# Newtech_Music_Board.net
KiCad netlist of a schematic drawn in EAGLE
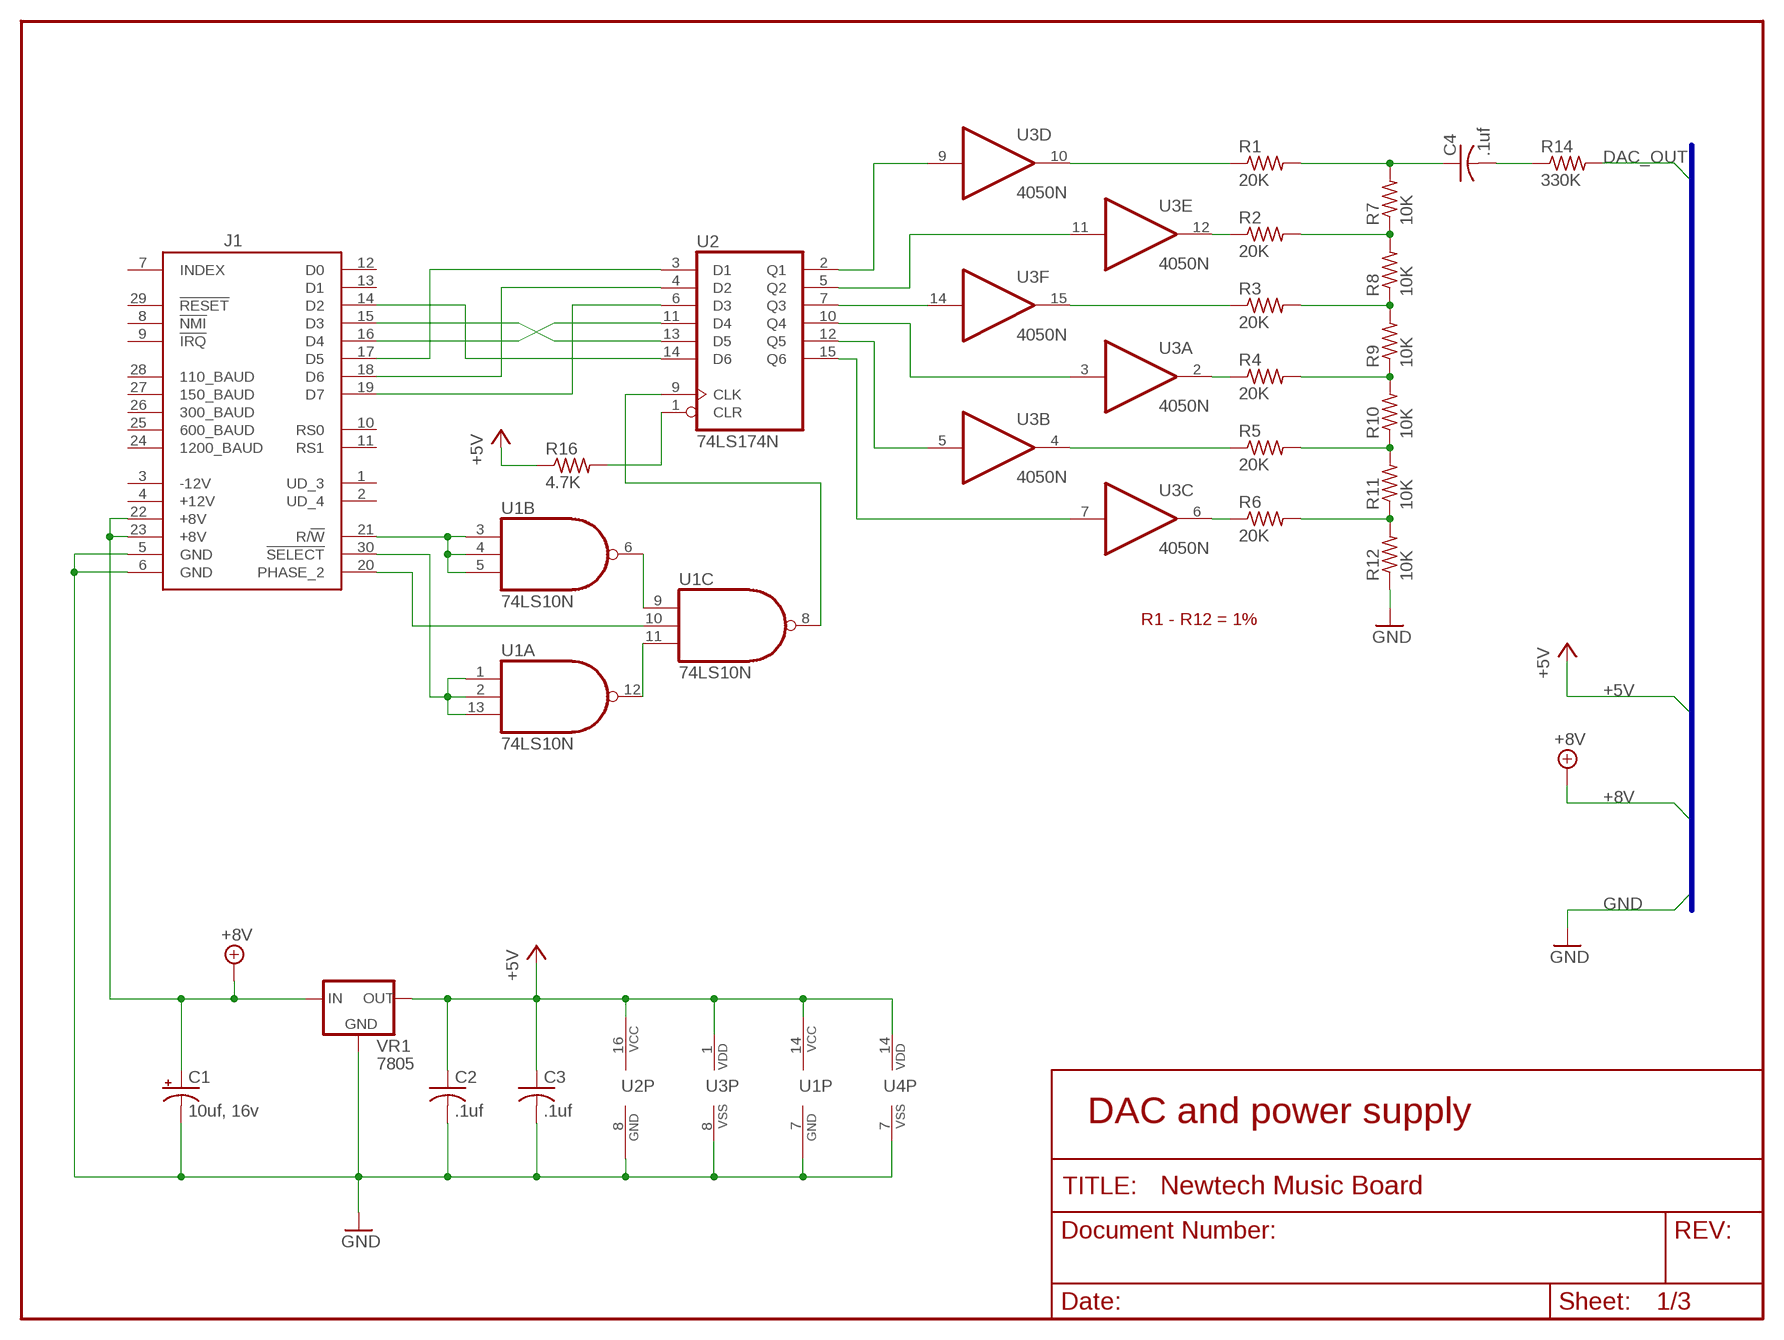
[diagram p0: schematic, sheet 1]
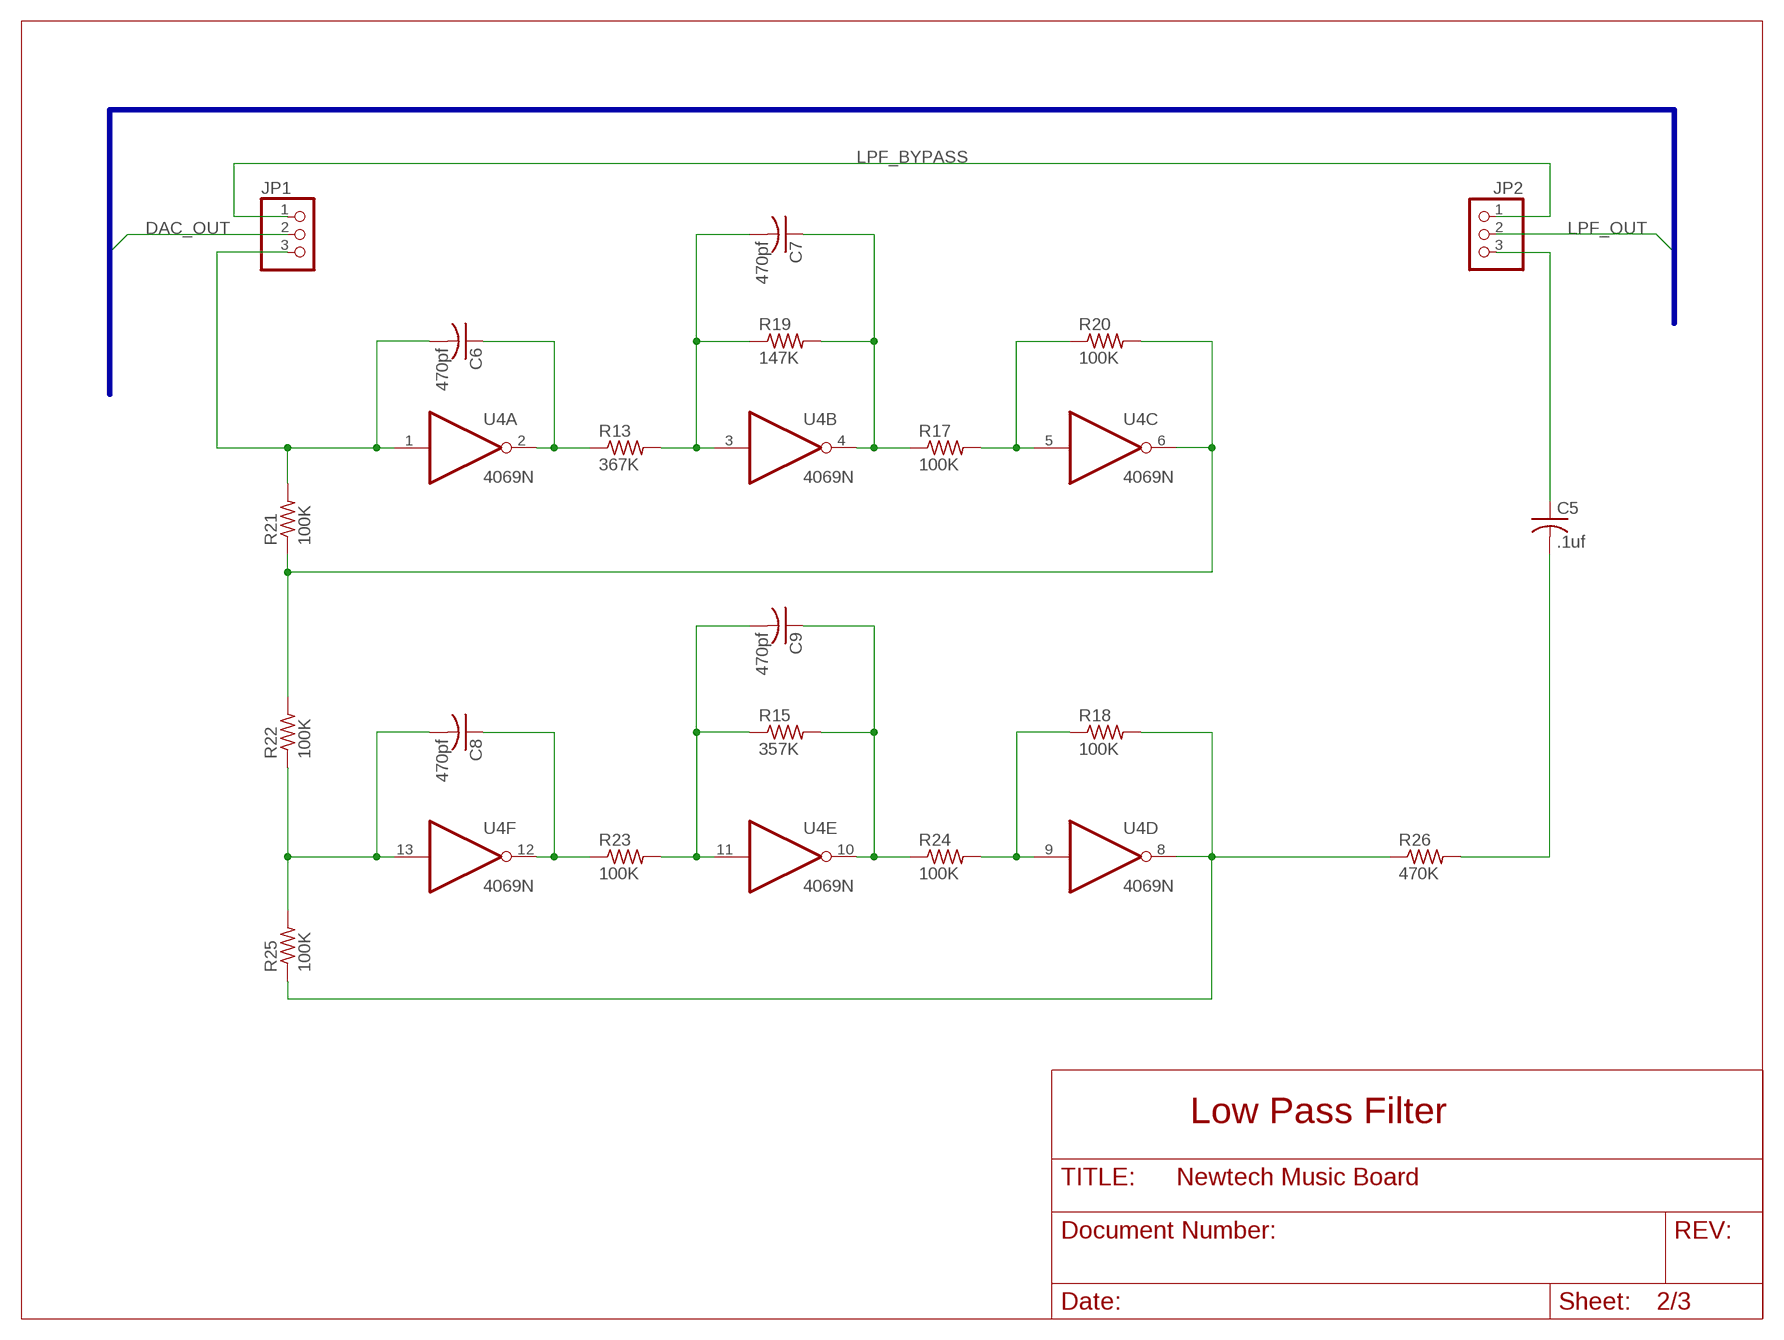
[diagram p1: schematic, sheet 2]
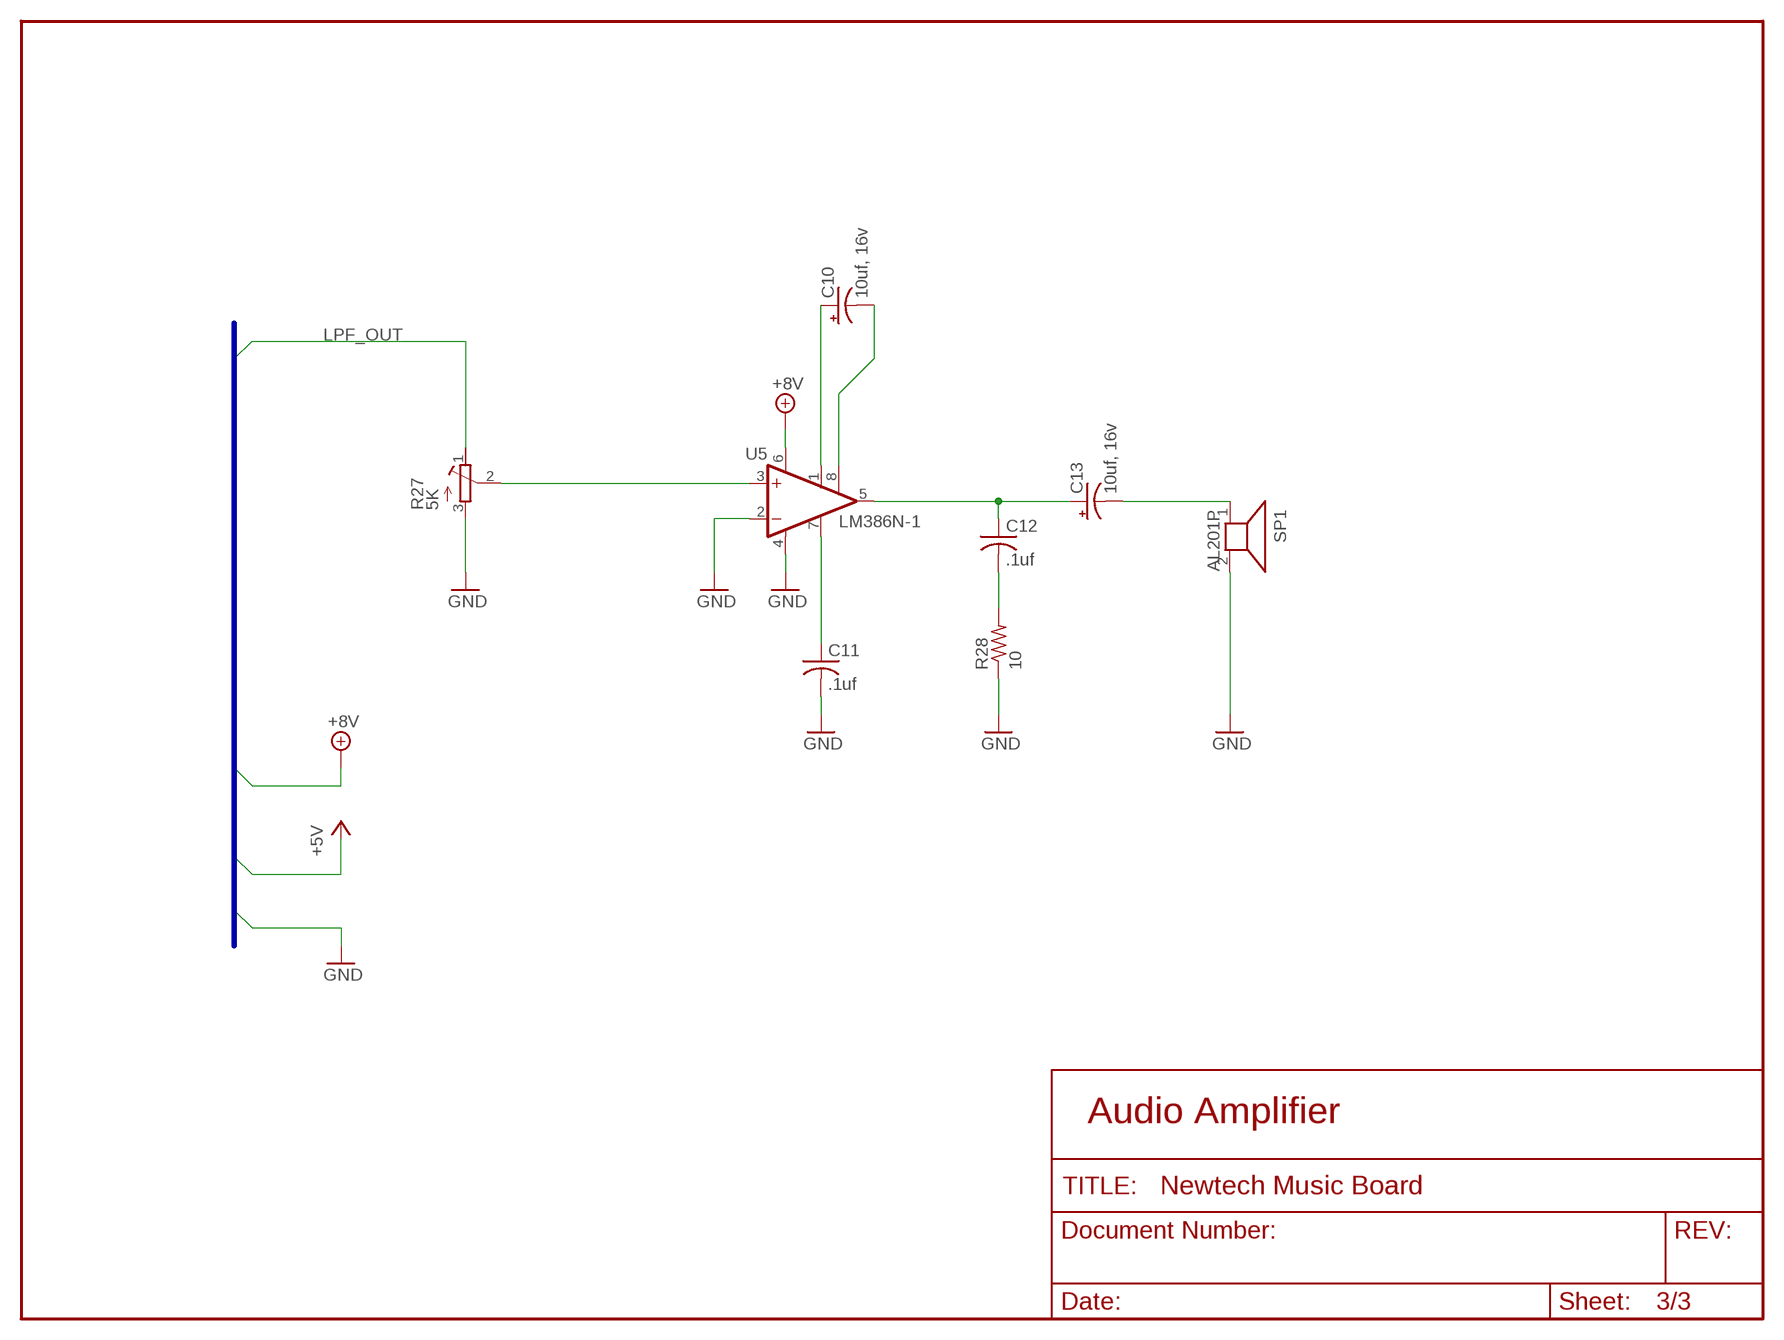
[diagram p2: schematic, sheet 3]

(export (version "E")
  (design (tool "Eeschema 10.0.6"))
  (components
    (comp (ref "C1")
      (value "10uf, 16v")
      (footprint "eagle-import:E2,5-6")
      (libsource (lib "eagle-import") (part "CPOL-USE2.5-6"))
    )
    (comp (ref "C2")
      (value ".1uf")
      (footprint "eagle-import:C025-025X050")
      (libsource (lib "eagle-import") (part "C-US025-025X050"))
    )
    (comp (ref "C3")
      (value ".1uf")
      (footprint "eagle-import:C025-025X050")
      (libsource (lib "eagle-import") (part "C-US025-025X050"))
    )
    (comp (ref "C4")
      (value ".1uf")
      (footprint "eagle-import:C025-024X044")
      (libsource (lib "eagle-import") (part "C-US025-024X044"))
    )
    (comp (ref "J1")
      (value "SS-30_BOARD_CONNECTOR")
      (footprint "eagle-import:SS-30_BOARD_CONNECTOR")
      (libsource (lib "eagle-import") (part "SS-30_BOARD_CONNECTOR"))
    )
    (comp (ref "R1")
      (value "20K")
      (footprint "eagle-import:0204_7")
      (libsource (lib "eagle-import") (part "R-US_0204/7"))
    )
    (comp (ref "R2")
      (value "20K")
      (footprint "eagle-import:0204_7")
      (libsource (lib "eagle-import") (part "R-US_0204/7"))
    )
    (comp (ref "R3")
      (value "20K")
      (footprint "eagle-import:0204_7")
      (libsource (lib "eagle-import") (part "R-US_0204/7"))
    )
    (comp (ref "R4")
      (value "20K")
      (footprint "eagle-import:0204_7")
      (libsource (lib "eagle-import") (part "R-US_0204/7"))
    )
    (comp (ref "R5")
      (value "20K")
      (footprint "eagle-import:0204_7")
      (libsource (lib "eagle-import") (part "R-US_0204/7"))
    )
    (comp (ref "R6")
      (value "20K")
      (footprint "eagle-import:0204_7")
      (libsource (lib "eagle-import") (part "R-US_0204/7"))
    )
    (comp (ref "R7")
      (value "10K")
      (footprint "eagle-import:0204_7")
      (libsource (lib "eagle-import") (part "R-US_0204/7"))
    )
    (comp (ref "R8")
      (value "10K")
      (footprint "eagle-import:0204_7")
      (libsource (lib "eagle-import") (part "R-US_0204/7"))
    )
    (comp (ref "R9")
      (value "10K")
      (footprint "eagle-import:0204_7")
      (libsource (lib "eagle-import") (part "R-US_0204/7"))
    )
    (comp (ref "R10")
      (value "10K")
      (footprint "eagle-import:0204_7")
      (libsource (lib "eagle-import") (part "R-US_0204/7"))
    )
    (comp (ref "R11")
      (value "10K")
      (footprint "eagle-import:0204_7")
      (libsource (lib "eagle-import") (part "R-US_0204/7"))
    )
    (comp (ref "R12")
      (value "10K")
      (footprint "eagle-import:0204_7")
      (libsource (lib "eagle-import") (part "R-US_0204/7"))
    )
    (comp (ref "R14")
      (value "330K")
      (footprint "eagle-import:0204_7")
      (libsource (lib "eagle-import") (part "R-US_0204/7"))
    )
    (comp (ref "R16")
      (value "4.7K")
      (footprint "eagle-import:0204_7")
      (libsource (lib "eagle-import") (part "R-US_0204/7"))
    )
    (comp (ref "U1")
      (value "74LS10N")
      (footprint "eagle-import:DIL14")
      (libsource (lib "eagle-import") (part "7410NLS"))
    )
    (comp (ref "U2")
      (value "74LS174N")
      (footprint "eagle-import:DIL16")
      (libsource (lib "eagle-import") (part "74174NLS"))
    )
    (comp (ref "U3")
      (value "4050N")
      (footprint "eagle-import:DIL16")
      (libsource (lib "eagle-import") (part "4050N"))
    )
    (comp (ref "U4")
      (value "4069N")
      (footprint "eagle-import:DIL14")
      (libsource (lib "eagle-import") (part "4069N"))
    )
    (comp (ref "VR1")
      (value "7805")
      (footprint "eagle-import:78XXL")
      (libsource (lib "eagle-import") (part "78XXL"))
    )
    (comp (ref "C5")
      (value ".1uf")
      (footprint "eagle-import:C025-025X050")
      (libsource (lib "eagle-import") (part "C-US025-025X050"))
    )
    (comp (ref "C6")
      (value "470pf")
      (footprint "eagle-import:C050-045X075")
      (libsource (lib "eagle-import") (part "C-US050-045X075"))
    )
    (comp (ref "C7")
      (value "470pf")
      (footprint "eagle-import:C050-045X075")
      (libsource (lib "eagle-import") (part "C-US050-045X075"))
    )
    (comp (ref "C8")
      (value "470pf")
      (footprint "eagle-import:C050-045X075")
      (libsource (lib "eagle-import") (part "C-US050-045X075"))
    )
    (comp (ref "C9")
      (value "470pf")
      (footprint "eagle-import:C050-045X075")
      (libsource (lib "eagle-import") (part "C-US050-045X075"))
    )
    (comp (ref "JP1")
      (value "PINHD-1X3")
      (footprint "eagle-import:1X03")
      (libsource (lib "eagle-import") (part "PINHD-1X3"))
    )
    (comp (ref "JP2")
      (value "PINHD-1X3")
      (footprint "eagle-import:1X03")
      (libsource (lib "eagle-import") (part "PINHD-1X3"))
    )
    (comp (ref "R13")
      (value "367K")
      (footprint "eagle-import:0204_7")
      (libsource (lib "eagle-import") (part "R-US_0204/7"))
    )
    (comp (ref "R15")
      (value "357K")
      (footprint "eagle-import:0204_7")
      (libsource (lib "eagle-import") (part "R-US_0204/7"))
    )
    (comp (ref "R17")
      (value "100K")
      (footprint "eagle-import:0204_7")
      (libsource (lib "eagle-import") (part "R-US_0204/7"))
    )
    (comp (ref "R18")
      (value "100K")
      (footprint "eagle-import:0204_7")
      (libsource (lib "eagle-import") (part "R-US_0204/7"))
    )
    (comp (ref "R19")
      (value "147K")
      (footprint "eagle-import:0204_7")
      (libsource (lib "eagle-import") (part "R-US_0204/7"))
    )
    (comp (ref "R20")
      (value "100K")
      (footprint "eagle-import:0204_7")
      (libsource (lib "eagle-import") (part "R-US_0204/7"))
    )
    (comp (ref "R21")
      (value "100K")
      (footprint "eagle-import:0204_7")
      (libsource (lib "eagle-import") (part "R-US_0204/7"))
    )
    (comp (ref "R22")
      (value "100K")
      (footprint "eagle-import:0204_7")
      (libsource (lib "eagle-import") (part "R-US_0204/7"))
    )
    (comp (ref "R23")
      (value "100K")
      (footprint "eagle-import:0204_7")
      (libsource (lib "eagle-import") (part "R-US_0204/7"))
    )
    (comp (ref "R24")
      (value "100K")
      (footprint "eagle-import:0204_7")
      (libsource (lib "eagle-import") (part "R-US_0204/7"))
    )
    (comp (ref "R25")
      (value "100K")
      (footprint "eagle-import:0204_7")
      (libsource (lib "eagle-import") (part "R-US_0204/7"))
    )
    (comp (ref "R26")
      (value "470K")
      (footprint "eagle-import:0204_7")
      (libsource (lib "eagle-import") (part "R-US_0204/7"))
    )
    (comp (ref "C10")
      (value "10uf, 16v")
      (footprint "eagle-import:E2,5-6")
      (libsource (lib "eagle-import") (part "CPOL-USE2.5-6"))
    )
    (comp (ref "C11")
      (value ".1uf")
      (footprint "eagle-import:C025-025X050")
      (libsource (lib "eagle-import") (part "C-US025-025X050"))
    )
    (comp (ref "C12")
      (value ".1uf")
      (footprint "eagle-import:C025-025X050")
      (libsource (lib "eagle-import") (part "C-US025-025X050"))
    )
    (comp (ref "C13")
      (value "10uf, 16v")
      (footprint "eagle-import:E2,5-6")
      (libsource (lib "eagle-import") (part "CPOL-USE2.5-6"))
    )
    (comp (ref "R27")
      (value "5K")
      (footprint "eagle-import:RTRIM43P")
      (libsource (lib "eagle-import") (part "R-TRIMM43P"))
    )
    (comp (ref "R28")
      (value "10")
      (footprint "eagle-import:0204_7")
      (libsource (lib "eagle-import") (part "R-US_0204/7"))
    )
    (comp (ref "SP1")
      (value "AL201P")
      (footprint "eagle-import:AL201P")
      (libsource (lib "eagle-import") (part "AL201P"))
    )
    (comp (ref "U5")
      (value "LM386N-1")
      (footprint "eagle-import:DIL08")
      (libsource (lib "eagle-import") (part "LM386?-N1"))
    )
  )
  (nets
    (net (code "1") (name "+5V") (class "Default")
      (node (ref "C2") (pin "1") (pinfunction "1_1") (pintype "passive"))
      (node (ref "C3") (pin "1") (pinfunction "1_1") (pintype "passive"))
      (node (ref "R16") (pin "1") (pinfunction "1_1") (pintype "passive"))
      (node (ref "U1") (pin "14") (pinfunction "VCC_14") (pintype "power_in"))
      (node (ref "U2") (pin "16") (pinfunction "VCC_16") (pintype "power_in"))
      (node (ref "U3") (pin "1") (pinfunction "VDD_1") (pintype "power_in"))
      (node (ref "U4") (pin "14") (pinfunction "VDD_14") (pintype "power_in"))
      (node (ref "VR1") (pin "OUT") (pinfunction "OUT_OUT") (pintype "passive"))
    )
    (net (code "2") (name "+8V") (class "Default")
      (node (ref "C1") (pin "+") (pinfunction "+_+") (pintype "passive"))
      (node (ref "J1") (pin "22") (pinfunction "+8V_22") (pintype "power_in"))
      (node (ref "J1") (pin "23") (pinfunction "+8V_23") (pintype "power_in"))
      (node (ref "U5") (pin "6") (pinfunction "VS_6") (pintype "power_in"))
      (node (ref "VR1") (pin "IN") (pinfunction "IN_IN") (pintype "input"))
    )
    (net (code "3") (name "+12V") (class "Default")
      (node (ref "J1") (pin "4") (pinfunction "+12V_4") (pintype "power_in"))
    )
    (net (code "4") (name "-12V") (class "Default")
      (node (ref "J1") (pin "3") (pinfunction "-12V_3") (pintype "power_in"))
    )
    (net (code "5") (name "DAC_OUT") (class "Default")
      (node (ref "JP1") (pin "2") (pinfunction "2_2") (pintype "passive"))
      (node (ref "R14") (pin "2") (pinfunction "2_2") (pintype "passive"))
    )
    (net (code "6") (name "GND") (class "Default")
      (node (ref "C1") (pin "-") (pinfunction "-_-") (pintype "passive"))
      (node (ref "C11") (pin "2") (pinfunction "2_2") (pintype "passive"))
      (node (ref "C2") (pin "2") (pinfunction "2_2") (pintype "passive"))
      (node (ref "C3") (pin "2") (pinfunction "2_2") (pintype "passive"))
      (node (ref "J1") (pin "5") (pinfunction "GND_5") (pintype "power_in"))
      (node (ref "J1") (pin "6") (pinfunction "GND_6") (pintype "power_in"))
      (node (ref "R12") (pin "1") (pinfunction "1_1") (pintype "passive"))
      (node (ref "R27") (pin "3") (pinfunction "E_3") (pintype "passive"))
      (node (ref "R28") (pin "1") (pinfunction "1_1") (pintype "passive"))
      (node (ref "SP1") (pin "2") (pinfunction "2_2") (pintype "passive"))
      (node (ref "U1") (pin "7") (pinfunction "GND_7") (pintype "power_in"))
      (node (ref "U2") (pin "8") (pinfunction "GND_8") (pintype "power_in"))
      (node (ref "U3") (pin "8") (pinfunction "VSS_8") (pintype "power_in"))
      (node (ref "U4") (pin "7") (pinfunction "VSS_7") (pintype "power_in"))
      (node (ref "U5") (pin "2") (pinfunction "-IN_2") (pintype "input"))
      (node (ref "U5") (pin "4") (pinfunction "GND_4") (pintype "power_in"))
      (node (ref "VR1") (pin "GND") (pinfunction "GND_GND") (pintype "input"))
    )
    (net (code "7") (name "LPF_BYPASS") (class "Default")
      (node (ref "JP1") (pin "1") (pinfunction "1_1") (pintype "passive"))
      (node (ref "JP2") (pin "1") (pinfunction "1_1") (pintype "passive"))
    )
    (net (code "8") (name "LPF_OUT") (class "Default")
      (node (ref "JP2") (pin "2") (pinfunction "2_2") (pintype "passive"))
      (node (ref "R27") (pin "1") (pinfunction "A_1") (pintype "passive"))
    )
    (net (code "9") (name "Net-(C4-Pad1)") (class "Default")
      (node (ref "C4") (pin "1") (pinfunction "1_1") (pintype "passive"))
      (node (ref "R1") (pin "2") (pinfunction "2_2") (pintype "passive"))
      (node (ref "R7") (pin "2") (pinfunction "2_2") (pintype "passive"))
    )
    (net (code "10") (name "Net-(C4-Pad2)") (class "Default")
      (node (ref "C4") (pin "2") (pinfunction "2_2") (pintype "passive"))
      (node (ref "R14") (pin "1") (pinfunction "1_1") (pintype "passive"))
    )
    (net (code "11") (name "Net-(C5-Pad1)") (class "Default")
      (node (ref "C5") (pin "1") (pinfunction "1_1") (pintype "passive"))
      (node (ref "JP2") (pin "3") (pinfunction "3_3") (pintype "passive"))
    )
    (net (code "12") (name "Net-(C5-Pad2)") (class "Default")
      (node (ref "C5") (pin "2") (pinfunction "2_2") (pintype "passive"))
      (node (ref "R26") (pin "2") (pinfunction "2_2") (pintype "passive"))
    )
    (net (code "13") (name "Net-(C10-Pad+)") (class "Default")
      (node (ref "C10") (pin "+") (pinfunction "+_+") (pintype "passive"))
      (node (ref "U5") (pin "1") (pinfunction "GAIN_1") (pintype "passive"))
    )
    (net (code "14") (name "Net-(C10-Pad-)") (class "Default")
      (node (ref "C10") (pin "-") (pinfunction "-_-") (pintype "passive"))
      (node (ref "U5") (pin "8") (pinfunction "GAIN_8") (pintype "passive"))
    )
    (net (code "15") (name "Net-(C12-Pad2)") (class "Default")
      (node (ref "C12") (pin "2") (pinfunction "2_2") (pintype "passive"))
      (node (ref "R28") (pin "2") (pinfunction "2_2") (pintype "passive"))
    )
    (net (code "16") (name "Net-(C13-Pad-)") (class "Default")
      (node (ref "C13") (pin "-") (pinfunction "-_-") (pintype "passive"))
      (node (ref "SP1") (pin "1") (pinfunction "1_1") (pintype "passive"))
    )
    (net (code "17") (name "Net-(J1-D2)") (class "Default")
      (node (ref "J1") (pin "14") (pinfunction "D2_14") (pintype "bidirectional"))
      (node (ref "U2") (pin "14") (pinfunction "D6_14") (pintype "input"))
    )
    (net (code "18") (name "Net-(J1-D3)") (class "Default")
      (node (ref "J1") (pin "15") (pinfunction "D3_15") (pintype "bidirectional"))
      (node (ref "U2") (pin "13") (pinfunction "D5_13") (pintype "input"))
    )
    (net (code "19") (name "Net-(J1-D4)") (class "Default")
      (node (ref "J1") (pin "16") (pinfunction "D4_16") (pintype "bidirectional"))
      (node (ref "U2") (pin "11") (pinfunction "D4_11") (pintype "input"))
    )
    (net (code "20") (name "Net-(J1-D5)") (class "Default")
      (node (ref "J1") (pin "17") (pinfunction "D5_17") (pintype "bidirectional"))
      (node (ref "U2") (pin "3") (pinfunction "D1_3") (pintype "input"))
    )
    (net (code "21") (name "Net-(J1-D6)") (class "Default")
      (node (ref "J1") (pin "18") (pinfunction "D6_18") (pintype "bidirectional"))
      (node (ref "U2") (pin "4") (pinfunction "D2_4") (pintype "input"))
    )
    (net (code "22") (name "Net-(J1-D7)") (class "Default")
      (node (ref "J1") (pin "19") (pinfunction "D7_19") (pintype "bidirectional"))
      (node (ref "U2") (pin "6") (pinfunction "D3_6") (pintype "input"))
    )
    (net (code "23") (name "Net-(J1-PHASE_2)") (class "Default")
      (node (ref "J1") (pin "20") (pinfunction "PHASE_2_20") (pintype "bidirectional"))
      (node (ref "U1") (pin "10") (pinfunction "I1_10") (pintype "input"))
    )
    (net (code "24") (name "Net-(J1-R{slash}~{W})") (class "Default")
      (node (ref "J1") (pin "21") (pinfunction "R/~{W}_21") (pintype "bidirectional"))
      (node (ref "U1") (pin "3") (pinfunction "I0_3") (pintype "input"))
      (node (ref "U1") (pin "4") (pinfunction "I1_4") (pintype "input"))
      (node (ref "U1") (pin "5") (pinfunction "I2_5") (pintype "input"))
    )
    (net (code "25") (name "Net-(J1-~{SELECT})") (class "Default")
      (node (ref "J1") (pin "30") (pinfunction "~{SELECT}_30") (pintype "bidirectional"))
      (node (ref "U1") (pin "1") (pinfunction "I0_1") (pintype "input"))
      (node (ref "U1") (pin "13") (pinfunction "I2_13") (pintype "input"))
      (node (ref "U1") (pin "2") (pinfunction "I1_2") (pintype "input"))
    )
    (net (code "26") (name "Net-(R2-Pad2)") (class "Default")
      (node (ref "R2") (pin "2") (pinfunction "2_2") (pintype "passive"))
      (node (ref "R7") (pin "1") (pinfunction "1_1") (pintype "passive"))
      (node (ref "R8") (pin "2") (pinfunction "2_2") (pintype "passive"))
    )
    (net (code "27") (name "Net-(R3-Pad2)") (class "Default")
      (node (ref "R3") (pin "2") (pinfunction "2_2") (pintype "passive"))
      (node (ref "R8") (pin "1") (pinfunction "1_1") (pintype "passive"))
      (node (ref "R9") (pin "2") (pinfunction "2_2") (pintype "passive"))
    )
    (net (code "28") (name "Net-(R10-Pad1)") (class "Default")
      (node (ref "R10") (pin "1") (pinfunction "1_1") (pintype "passive"))
      (node (ref "R11") (pin "2") (pinfunction "2_2") (pintype "passive"))
      (node (ref "R5") (pin "2") (pinfunction "2_2") (pintype "passive"))
    )
    (net (code "29") (name "Net-(R10-Pad2)") (class "Default")
      (node (ref "R10") (pin "2") (pinfunction "2_2") (pintype "passive"))
      (node (ref "R4") (pin "2") (pinfunction "2_2") (pintype "passive"))
      (node (ref "R9") (pin "1") (pinfunction "1_1") (pintype "passive"))
    )
    (net (code "30") (name "Net-(R11-Pad1)") (class "Default")
      (node (ref "R11") (pin "1") (pinfunction "1_1") (pintype "passive"))
      (node (ref "R12") (pin "2") (pinfunction "2_2") (pintype "passive"))
      (node (ref "R6") (pin "2") (pinfunction "2_2") (pintype "passive"))
    )
    (net (code "31") (name "Net-(R27-S)") (class "Default")
      (node (ref "R27") (pin "2") (pinfunction "S_2") (pintype "passive"))
      (node (ref "U5") (pin "3") (pinfunction "+IN_3") (pintype "input"))
    )
    (net (code "32") (name "Net-(U1A-O)") (class "Default")
      (node (ref "U1") (pin "11") (pinfunction "I2_11") (pintype "input"))
      (node (ref "U1") (pin "12") (pinfunction "O_12") (pintype "output"))
    )
    (net (code "33") (name "Net-(U1B-O)") (class "Default")
      (node (ref "U1") (pin "6") (pinfunction "O_6") (pintype "output"))
      (node (ref "U1") (pin "9") (pinfunction "I0_9") (pintype "input"))
    )
    (net (code "34") (name "Net-(U1C-O)") (class "Default")
      (node (ref "U1") (pin "8") (pinfunction "O_8") (pintype "output"))
      (node (ref "U2") (pin "9") (pinfunction "CLK_9") (pintype "input"))
    )
    (net (code "35") (name "Net-(U2A-CLR)") (class "Default")
      (node (ref "R16") (pin "2") (pinfunction "2_2") (pintype "passive"))
      (node (ref "U2") (pin "1") (pinfunction "CLR_1") (pintype "input"))
    )
    (net (code "36") (name "Net-(U2A-Q1)") (class "Default")
      (node (ref "U2") (pin "2") (pinfunction "Q1_2") (pintype "output"))
      (node (ref "U3") (pin "9") (pinfunction "I_9") (pintype "input"))
    )
    (net (code "37") (name "Net-(U2A-Q2)") (class "Default")
      (node (ref "U2") (pin "5") (pinfunction "Q2_5") (pintype "output"))
      (node (ref "U3") (pin "11") (pinfunction "I_11") (pintype "input"))
    )
    (net (code "38") (name "Net-(U2A-Q3)") (class "Default")
      (node (ref "U2") (pin "7") (pinfunction "Q3_7") (pintype "output"))
      (node (ref "U3") (pin "14") (pinfunction "I_14") (pintype "input"))
    )
    (net (code "39") (name "Net-(U2A-Q4)") (class "Default")
      (node (ref "U2") (pin "10") (pinfunction "Q4_10") (pintype "output"))
      (node (ref "U3") (pin "3") (pinfunction "I_3") (pintype "input"))
    )
    (net (code "40") (name "Net-(U2A-Q5)") (class "Default")
      (node (ref "U2") (pin "12") (pinfunction "Q5_12") (pintype "output"))
      (node (ref "U3") (pin "5") (pinfunction "I_5") (pintype "input"))
    )
    (net (code "41") (name "Net-(U2A-Q6)") (class "Default")
      (node (ref "U2") (pin "15") (pinfunction "Q6_15") (pintype "output"))
      (node (ref "U3") (pin "7") (pinfunction "I_7") (pintype "input"))
    )
    (net (code "42") (name "Net-(U3A-O)") (class "Default")
      (node (ref "R4") (pin "1") (pinfunction "1_1") (pintype "passive"))
      (node (ref "U3") (pin "2") (pinfunction "O_2") (pintype "output"))
    )
    (net (code "43") (name "Net-(U3B-O)") (class "Default")
      (node (ref "R5") (pin "1") (pinfunction "1_1") (pintype "passive"))
      (node (ref "U3") (pin "4") (pinfunction "O_4") (pintype "output"))
    )
    (net (code "44") (name "Net-(U3C-O)") (class "Default")
      (node (ref "R6") (pin "1") (pinfunction "1_1") (pintype "passive"))
      (node (ref "U3") (pin "6") (pinfunction "O_6") (pintype "output"))
    )
    (net (code "45") (name "Net-(U3D-O)") (class "Default")
      (node (ref "R1") (pin "1") (pinfunction "1_1") (pintype "passive"))
      (node (ref "U3") (pin "10") (pinfunction "O_10") (pintype "output"))
    )
    (net (code "46") (name "Net-(U3E-O)") (class "Default")
      (node (ref "R2") (pin "1") (pinfunction "1_1") (pintype "passive"))
      (node (ref "U3") (pin "12") (pinfunction "O_12") (pintype "output"))
    )
    (net (code "47") (name "Net-(U3F-O)") (class "Default")
      (node (ref "R3") (pin "1") (pinfunction "1_1") (pintype "passive"))
      (node (ref "U3") (pin "15") (pinfunction "O_15") (pintype "output"))
    )
    (net (code "48") (name "Net-(U4A-I)") (class "Default")
      (node (ref "C6") (pin "2") (pinfunction "2_2") (pintype "passive"))
      (node (ref "JP1") (pin "3") (pinfunction "3_3") (pintype "passive"))
      (node (ref "R21") (pin "2") (pinfunction "2_2") (pintype "passive"))
      (node (ref "U4") (pin "1") (pinfunction "I_1") (pintype "input"))
    )
    (net (code "49") (name "Net-(U4A-O)") (class "Default")
      (node (ref "C6") (pin "1") (pinfunction "1_1") (pintype "passive"))
      (node (ref "R13") (pin "1") (pinfunction "1_1") (pintype "passive"))
      (node (ref "U4") (pin "2") (pinfunction "O_2") (pintype "output"))
    )
    (net (code "50") (name "Net-(U4B-I)") (class "Default")
      (node (ref "C7") (pin "2") (pinfunction "2_2") (pintype "passive"))
      (node (ref "R13") (pin "2") (pinfunction "2_2") (pintype "passive"))
      (node (ref "R19") (pin "1") (pinfunction "1_1") (pintype "passive"))
      (node (ref "U4") (pin "3") (pinfunction "I_3") (pintype "input"))
    )
    (net (code "51") (name "Net-(U4B-O)") (class "Default")
      (node (ref "C7") (pin "1") (pinfunction "1_1") (pintype "passive"))
      (node (ref "R17") (pin "1") (pinfunction "1_1") (pintype "passive"))
      (node (ref "R19") (pin "2") (pinfunction "2_2") (pintype "passive"))
      (node (ref "U4") (pin "4") (pinfunction "O_4") (pintype "output"))
    )
    (net (code "52") (name "Net-(U4C-I)") (class "Default")
      (node (ref "R17") (pin "2") (pinfunction "2_2") (pintype "passive"))
      (node (ref "R20") (pin "1") (pinfunction "1_1") (pintype "passive"))
      (node (ref "U4") (pin "5") (pinfunction "I_5") (pintype "input"))
    )
    (net (code "53") (name "Net-(U4C-O)") (class "Default")
      (node (ref "R20") (pin "2") (pinfunction "2_2") (pintype "passive"))
      (node (ref "R21") (pin "1") (pinfunction "1_1") (pintype "passive"))
      (node (ref "R22") (pin "2") (pinfunction "2_2") (pintype "passive"))
      (node (ref "U4") (pin "6") (pinfunction "O_6") (pintype "output"))
    )
    (net (code "54") (name "Net-(U4D-I)") (class "Default")
      (node (ref "R18") (pin "1") (pinfunction "1_1") (pintype "passive"))
      (node (ref "R24") (pin "2") (pinfunction "2_2") (pintype "passive"))
      (node (ref "U4") (pin "9") (pinfunction "I_9") (pintype "input"))
    )
    (net (code "55") (name "Net-(U4D-O)") (class "Default")
      (node (ref "R18") (pin "2") (pinfunction "2_2") (pintype "passive"))
      (node (ref "R25") (pin "1") (pinfunction "1_1") (pintype "passive"))
      (node (ref "R26") (pin "1") (pinfunction "1_1") (pintype "passive"))
      (node (ref "U4") (pin "8") (pinfunction "O_8") (pintype "output"))
    )
    (net (code "56") (name "Net-(U4E-I)") (class "Default")
      (node (ref "C9") (pin "2") (pinfunction "2_2") (pintype "passive"))
      (node (ref "R15") (pin "1") (pinfunction "1_1") (pintype "passive"))
      (node (ref "R23") (pin "2") (pinfunction "2_2") (pintype "passive"))
      (node (ref "U4") (pin "11") (pinfunction "I_11") (pintype "input"))
    )
    (net (code "57") (name "Net-(U4E-O)") (class "Default")
      (node (ref "C9") (pin "1") (pinfunction "1_1") (pintype "passive"))
      (node (ref "R15") (pin "2") (pinfunction "2_2") (pintype "passive"))
      (node (ref "R24") (pin "1") (pinfunction "1_1") (pintype "passive"))
      (node (ref "U4") (pin "10") (pinfunction "O_10") (pintype "output"))
    )
    (net (code "58") (name "Net-(U4F-I)") (class "Default")
      (node (ref "C8") (pin "2") (pinfunction "2_2") (pintype "passive"))
      (node (ref "R22") (pin "1") (pinfunction "1_1") (pintype "passive"))
      (node (ref "R25") (pin "2") (pinfunction "2_2") (pintype "passive"))
      (node (ref "U4") (pin "13") (pinfunction "I_13") (pintype "input"))
    )
    (net (code "59") (name "Net-(U4F-O)") (class "Default")
      (node (ref "C8") (pin "1") (pinfunction "1_1") (pintype "passive"))
      (node (ref "R23") (pin "1") (pinfunction "1_1") (pintype "passive"))
      (node (ref "U4") (pin "12") (pinfunction "O_12") (pintype "output"))
    )
    (net (code "60") (name "Net-(U5-BYPASS)") (class "Default")
      (node (ref "C11") (pin "1") (pinfunction "1_1") (pintype "passive"))
      (node (ref "U5") (pin "7") (pinfunction "BYPASS_7") (pintype "passive"))
    )
    (net (code "61") (name "Net-(U5-OUT)") (class "Default")
      (node (ref "C12") (pin "1") (pinfunction "1_1") (pintype "passive"))
      (node (ref "C13") (pin "+") (pinfunction "+_+") (pintype "passive"))
      (node (ref "U5") (pin "5") (pinfunction "OUT_5") (pintype "output"))
    )
    (net (code "62") (name "unconnected-(J1-110_BAUD-Pad28)") (class "Default")
      (node (ref "J1") (pin "28") (pinfunction "110_BAUD_28") (pintype "bidirectional"))
    )
    (net (code "63") (name "unconnected-(J1-150_BAUD-Pad27)") (class "Default")
      (node (ref "J1") (pin "27") (pinfunction "150_BAUD_27") (pintype "bidirectional"))
    )
    (net (code "64") (name "unconnected-(J1-300_BAUD-Pad26)") (class "Default")
      (node (ref "J1") (pin "26") (pinfunction "300_BAUD_26") (pintype "bidirectional"))
    )
    (net (code "65") (name "unconnected-(J1-600_BAUD-Pad25)") (class "Default")
      (node (ref "J1") (pin "25") (pinfunction "600_BAUD_25") (pintype "bidirectional"))
    )
    (net (code "66") (name "unconnected-(J1-1200_BAUD-Pad24)") (class "Default")
      (node (ref "J1") (pin "24") (pinfunction "1200_BAUD_24") (pintype "bidirectional"))
    )
    (net (code "67") (name "unconnected-(J1-D0-Pad12)") (class "Default")
      (node (ref "J1") (pin "12") (pinfunction "D0_12") (pintype "bidirectional"))
    )
    (net (code "68") (name "unconnected-(J1-D1-Pad13)") (class "Default")
      (node (ref "J1") (pin "13") (pinfunction "D1_13") (pintype "bidirectional"))
    )
    (net (code "69") (name "unconnected-(J1-INDEX-Pad7)") (class "Default")
      (node (ref "J1") (pin "7") (pinfunction "INDEX_7") (pintype "no_connect"))
    )
    (net (code "70") (name "unconnected-(J1-RS0-Pad10)") (class "Default")
      (node (ref "J1") (pin "10") (pinfunction "RS0_10") (pintype "bidirectional"))
    )
    (net (code "71") (name "unconnected-(J1-RS1-Pad11)") (class "Default")
      (node (ref "J1") (pin "11") (pinfunction "RS1_11") (pintype "bidirectional"))
    )
    (net (code "72") (name "unconnected-(J1-UD_3-Pad1)") (class "Default")
      (node (ref "J1") (pin "1") (pinfunction "UD_3_1") (pintype "bidirectional"))
    )
    (net (code "73") (name "unconnected-(J1-UD_4-Pad2)") (class "Default")
      (node (ref "J1") (pin "2") (pinfunction "UD_4_2") (pintype "bidirectional"))
    )
    (net (code "74") (name "unconnected-(J1-~{IRQ}-Pad9)") (class "Default")
      (node (ref "J1") (pin "9") (pinfunction "~{IRQ}_9") (pintype "bidirectional"))
    )
    (net (code "75") (name "unconnected-(J1-~{NMI}-Pad8)") (class "Default")
      (node (ref "J1") (pin "8") (pinfunction "~{NMI}_8") (pintype "bidirectional"))
    )
    (net (code "76") (name "unconnected-(J1-~{RESET}-Pad29)") (class "Default")
      (node (ref "J1") (pin "29") (pinfunction "~{RESET}_29") (pintype "bidirectional"))
    )
  )
)
